# FNR_Controller_v0_0_-_Original.net
KiCad netlist of a schematic drawn in EAGLE
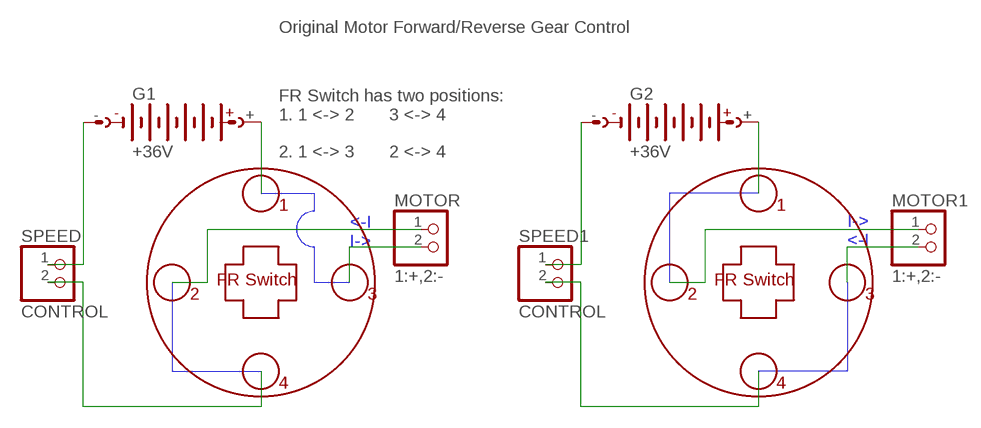
[diagram p0: schematic, sheet 1]

(export (version "E")
  (design (tool "Eeschema 10.0.6"))
  (components
    (comp (ref "G1")
      (value "+36V")
      (footprint "eagle-import:AB9V")
      (libsource (lib "eagle-import") (part "AB9V"))
    )
    (comp (ref "G2")
      (value "+36V")
      (footprint "eagle-import:AB9V")
      (libsource (lib "eagle-import") (part "AB9V"))
    )
    (comp (ref "MOTOR")
      (value "1:+,2:-")
      (footprint "eagle-import:1X02")
      (libsource (lib "eagle-import") (part "PINHD-1X2"))
    )
    (comp (ref "MOTOR1")
      (value "1:+,2:-")
      (footprint "eagle-import:1X02")
      (libsource (lib "eagle-import") (part "PINHD-1X2"))
    )
    (comp (ref "SPEED")
      (value "CONTROL")
      (footprint "eagle-import:1X02")
      (libsource (lib "eagle-import") (part "PINHD-1X2"))
    )
    (comp (ref "SPEED1")
      (value "CONTROL")
      (footprint "eagle-import:1X02")
      (libsource (lib "eagle-import") (part "PINHD-1X2"))
    )
    (comp (ref "U$1")
      (value "FRSWITCH")
      (footprint "eagle-import:DIL08-ROUND")
      (libsource (lib "eagle-import") (part "FRSWITCH"))
    )
    (comp (ref "U$3")
      (value "FRSWITCH")
      (footprint "eagle-import:DIL08-ROUND")
      (libsource (lib "eagle-import") (part "FRSWITCH"))
    )
  )
  (nets
    (net (code "1") (name "Net-(G1-Pad-)") (class "Default")
      (node (ref "G1") (pin "-") (pinfunction "-_-") (pintype "passive"))
      (node (ref "SPEED") (pin "1") (pinfunction "1_1") (pintype "passive"))
    )
    (net (code "2") (name "Net-(G2-Pad-)") (class "Default")
      (node (ref "G2") (pin "-") (pinfunction "-_-") (pintype "passive"))
      (node (ref "SPEED1") (pin "1") (pinfunction "1_1") (pintype "passive"))
    )
    (net (code "3") (name "Net-(U$1-P$1)") (class "Default")
      (node (ref "G1") (pin "+") (pinfunction "+_+") (pintype "passive"))
      (node (ref "U$1") (pin "1") (pinfunction "P$1_1") (pintype "bidirectional"))
    )
    (net (code "4") (name "Net-(U$1-P$2)") (class "Default")
      (node (ref "MOTOR") (pin "2") (pinfunction "2_2") (pintype "passive"))
      (node (ref "U$1") (pin "2") (pinfunction "P$2_2") (pintype "bidirectional"))
    )
    (net (code "5") (name "Net-(U$1-P$3)") (class "Default")
      (node (ref "MOTOR") (pin "1") (pinfunction "1_1") (pintype "passive"))
      (node (ref "U$1") (pin "3") (pinfunction "P$3_3") (pintype "bidirectional"))
    )
    (net (code "6") (name "Net-(U$1-P$4)") (class "Default")
      (node (ref "SPEED") (pin "2") (pinfunction "2_2") (pintype "passive"))
      (node (ref "U$1") (pin "4") (pinfunction "P$4_4") (pintype "bidirectional"))
    )
    (net (code "7") (name "Net-(U$3-P$1)") (class "Default")
      (node (ref "G2") (pin "+") (pinfunction "+_+") (pintype "passive"))
      (node (ref "U$3") (pin "1") (pinfunction "P$1_1") (pintype "bidirectional"))
    )
    (net (code "8") (name "Net-(U$3-P$2)") (class "Default")
      (node (ref "MOTOR1") (pin "2") (pinfunction "2_2") (pintype "passive"))
      (node (ref "U$3") (pin "2") (pinfunction "P$2_2") (pintype "bidirectional"))
    )
    (net (code "9") (name "Net-(U$3-P$3)") (class "Default")
      (node (ref "MOTOR1") (pin "1") (pinfunction "1_1") (pintype "passive"))
      (node (ref "U$3") (pin "3") (pinfunction "P$3_3") (pintype "bidirectional"))
    )
    (net (code "10") (name "Net-(U$3-P$4)") (class "Default")
      (node (ref "SPEED1") (pin "2") (pinfunction "2_2") (pintype "passive"))
      (node (ref "U$3") (pin "4") (pinfunction "P$4_4") (pintype "bidirectional"))
    )
  )
)
